# 11_RK3128_CODEC_HDMI_DAC.net
KiCad netlist of a schematic drawn in Altium Designer
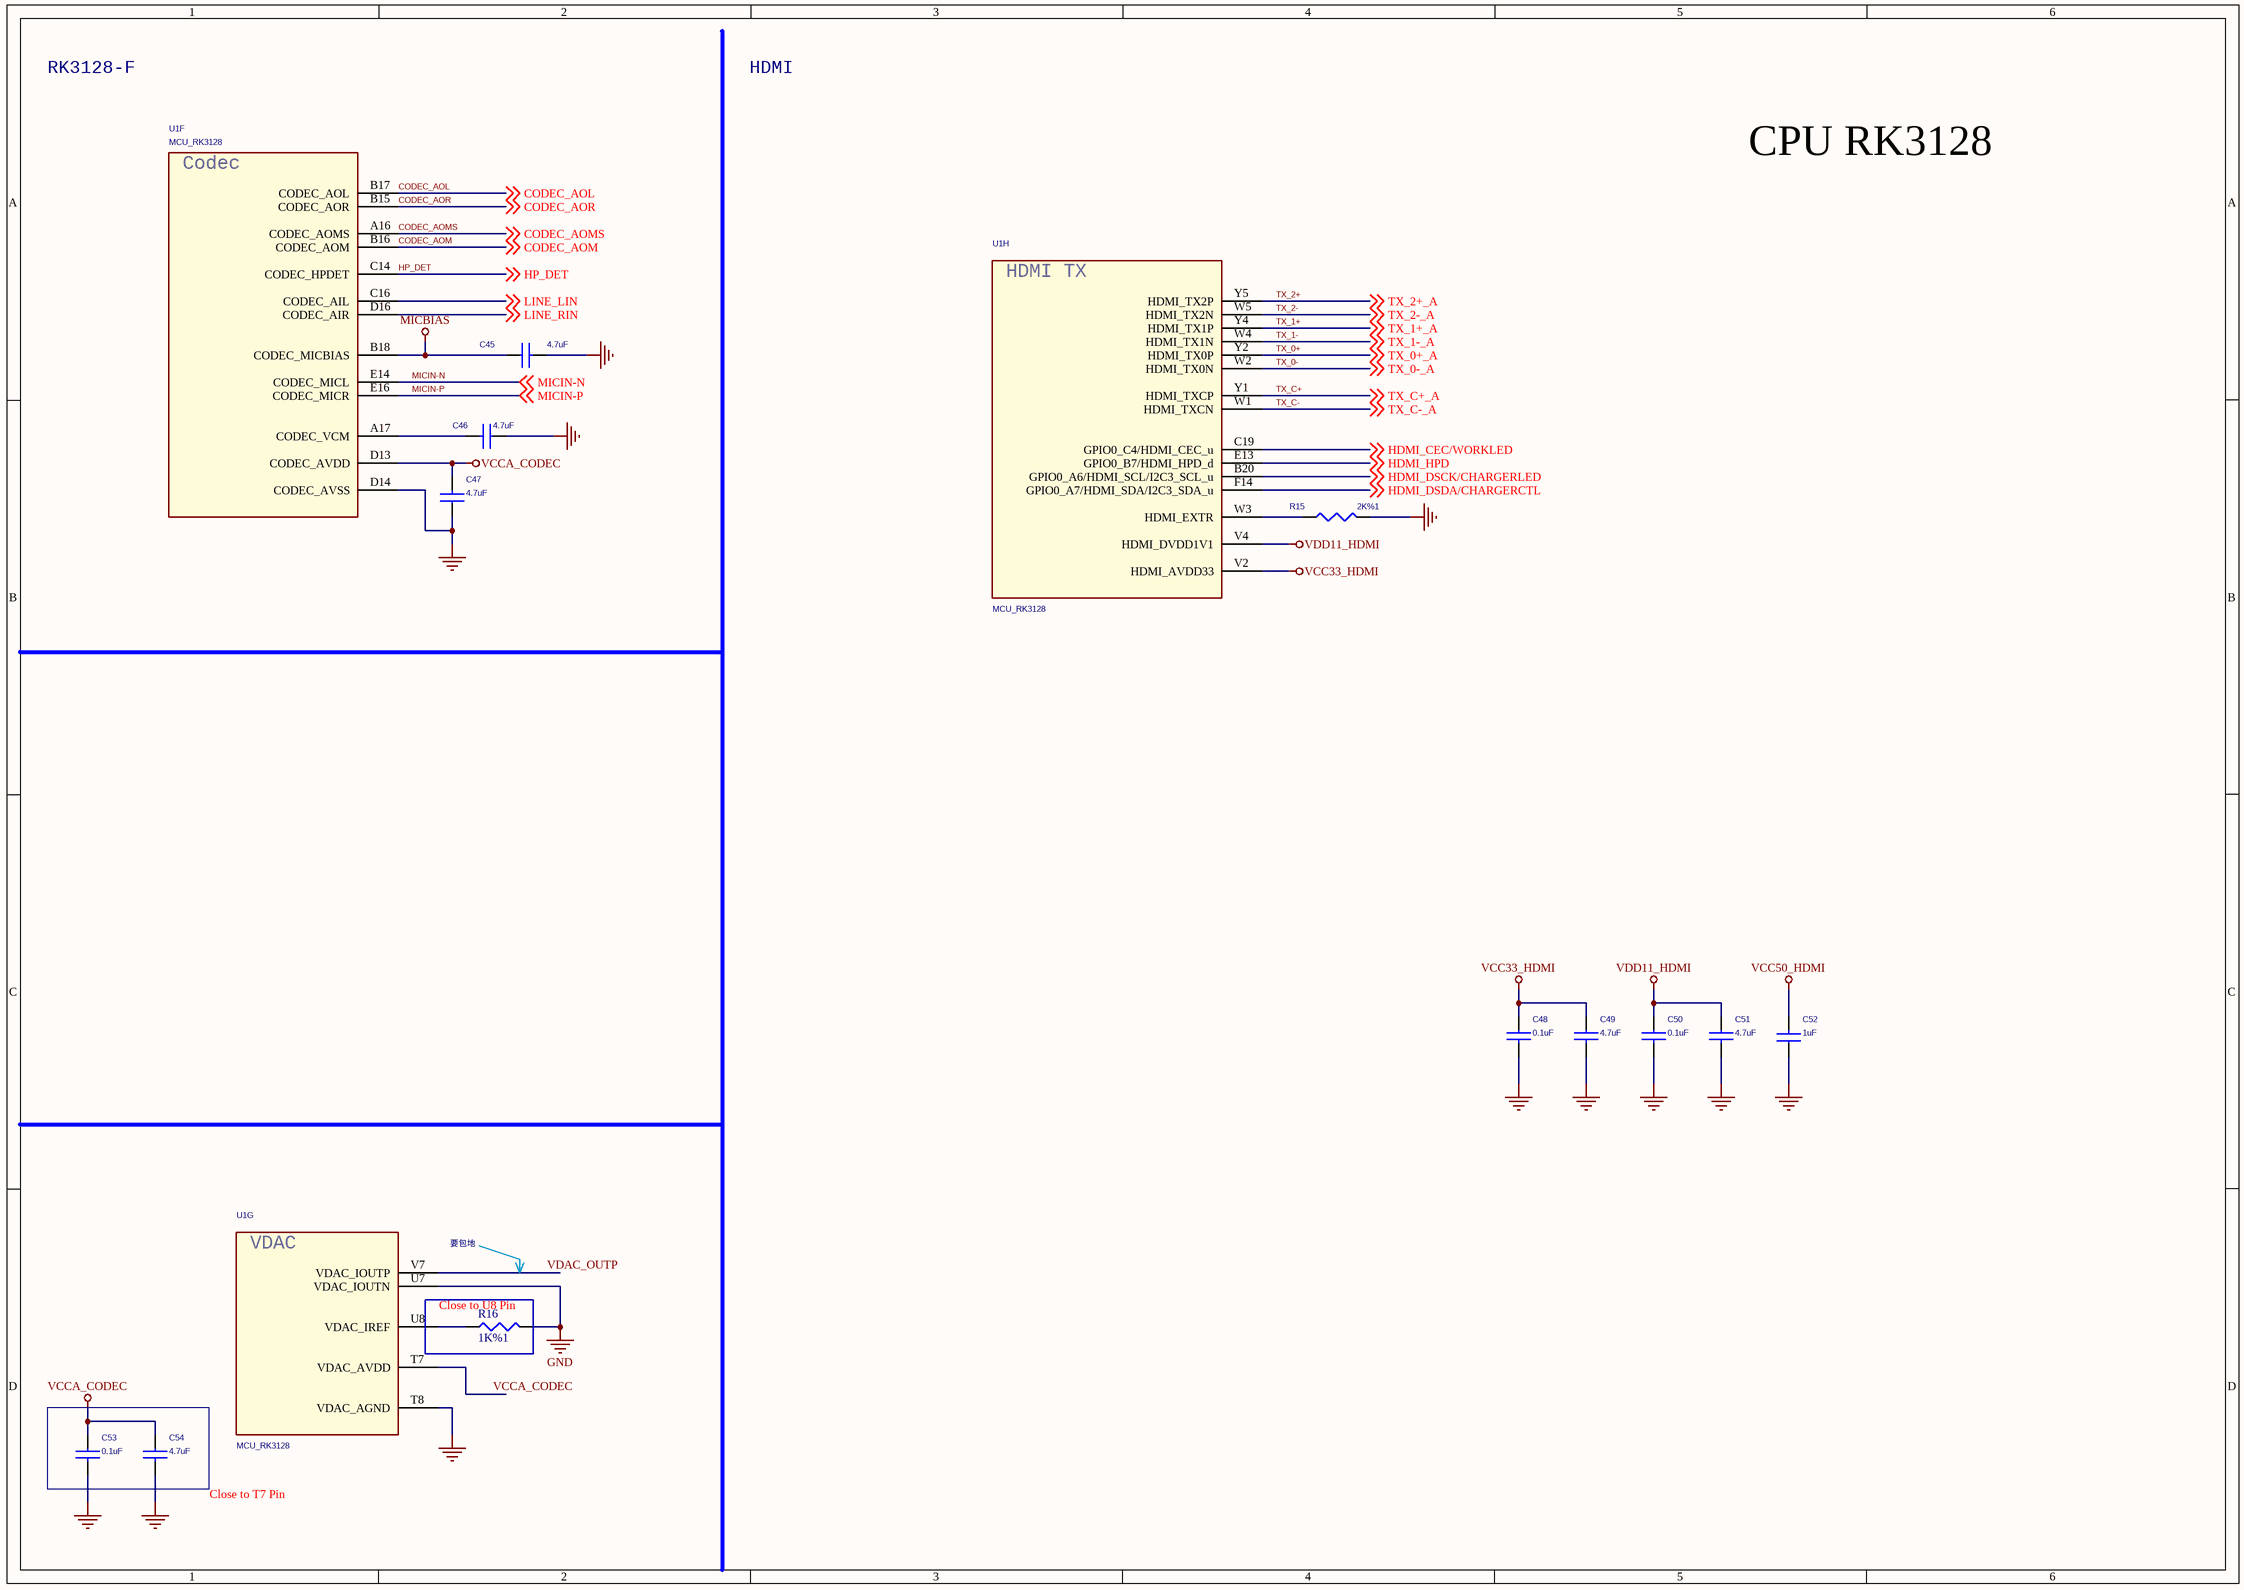
[diagram p0: 11_RK3128_CODEC_HDMI_DAC.SchDoc]

(export (version "E")
  (design (tool "Eeschema 10.0.6"))
  (components
    (comp (ref "C45") (value "4.7uF") (footprint "C0603") (libsource (lib "*") (part "CAP NP")))
    (comp (ref "C46")
      (value "4.7uF")
      (footprint "C0603")
      (description "CAP,MLCC,10uF,+/-10%,X5R,16V,SMD0805")
      (libsource (lib "*") (part "CAP NP"))
    )
    (comp (ref "C47")
      (value "4.7uF")
      (footprint "C0603")
      (description "RoHS CHIP CAP 0.1uF +10/-10% X7R")
      (libsource (lib "*") (part "CAP NP"))
    )
    (comp (ref "C48") (value "0.1uF") (footprint "C0402") (libsource (lib "*") (part "CAP NP")))
    (comp (ref "C49") (value "4.7uF") (footprint "C0603") (libsource (lib "*") (part "CAP NP")))
    (comp (ref "C50") (value "0.1uF") (footprint "C0402") (libsource (lib "*") (part "CAP NP")))
    (comp (ref "C51") (value "4.7uF") (footprint "C0603") (libsource (lib "*") (part "CAP NP")))
    (comp (ref "C52")
      (value "1uF")
      (footprint "C0402")
      (description "RoHS CHIP CAP 1uF +10/-10% X5R")
      (libsource (lib "*") (part "CAP NP"))
    )
    (comp (ref "C53") (value "0.1uF") (footprint "C0402") (libsource (lib "*") (part "CAP NP")))
    (comp (ref "C54") (value "4.7uF") (footprint "C0603") (libsource (lib "*") (part "CAP NP")))
    (comp (ref "R15")
      (value "2K%1")
      (footprint "R0402")
      (description "RES,thick film,3.5KOhm,+/-5%,1/16W,SMD0402")
      (libsource (lib "*") (part "RESISTOR_0"))
    )
    (comp (ref "R16")
      (value "1K%1")
      (footprint "R0402")
      (description "1K %1 R0402")
      (libsource (lib "RK3128_BETA_V03_20151231_Library") (part "RESISTOR"))
    )
    (comp (ref "U1")
      (value "MCU_RK3128")
      (footprint "BGA316-14X14-0.65")
      (libsource (lib "*") (part "MCU_RK3128"))
    )
  )
  (nets
    (net (code "1") (name "/VDAC_OUTP") (class "Default")
      (node (ref "U1") (pin "V7") (pinfunction "VDAC_IOUTP_V7") (pintype "passive"))
    )
    (net (code "2") (name "CODEC_AOL") (class "Default")
      (node (ref "U1") (pin "B17") (pinfunction "CODEC_AOL_B17") (pintype "passive"))
    )
    (net (code "3") (name "CODEC_AOM") (class "Default")
      (node (ref "U1") (pin "B16") (pinfunction "CODEC_AOM_B16") (pintype "passive"))
    )
    (net (code "4") (name "CODEC_AOMS") (class "Default")
      (node (ref "U1") (pin "A16") (pinfunction "CODEC_AOMS_A16") (pintype "passive"))
    )
    (net (code "5") (name "CODEC_AOR") (class "Default")
      (node (ref "U1") (pin "B15") (pinfunction "CODEC_AOR_B15") (pintype "passive"))
    )
    (net (code "6") (name "GND") (class "Default")
      (node (ref "C45") (pin "2") (pinfunction "2_2") (pintype "passive"))
      (node (ref "C46") (pin "1") (pinfunction "1_1") (pintype "passive"))
      (node (ref "C47") (pin "1") (pinfunction "1_1") (pintype "passive"))
      (node (ref "C48") (pin "2") (pinfunction "2_2") (pintype "passive"))
      (node (ref "C49") (pin "2") (pinfunction "2_2") (pintype "passive"))
      (node (ref "C50") (pin "2") (pinfunction "2_2") (pintype "passive"))
      (node (ref "C51") (pin "2") (pinfunction "2_2") (pintype "passive"))
      (node (ref "C52") (pin "1") (pinfunction "1_1") (pintype "passive"))
      (node (ref "C53") (pin "2") (pinfunction "2_2") (pintype "passive"))
      (node (ref "C54") (pin "2") (pinfunction "2_2") (pintype "passive"))
      (node (ref "R15") (pin "1") (pinfunction "1_1") (pintype "passive"))
      (node (ref "R16") (pin "2") (pinfunction "2_2") (pintype "passive"))
      (node (ref "U1") (pin "D14") (pinfunction "CODEC_AVSS_D14") (pintype "passive"))
      (node (ref "U1") (pin "T8") (pinfunction "VDAC_AGND_T8") (pintype "passive"))
      (node (ref "U1") (pin "U7") (pinfunction "VDAC_IOUTN_U7") (pintype "passive"))
    )
    (net (code "7") (name "HDMI_CEC{slash}WORKLED") (class "Default")
      (node (ref "U1") (pin "C19") (pinfunction "GPIO0_C4/HDMI_CEC_u_C19") (pintype "passive"))
    )
    (net (code "8") (name "HDMI_DSCK{slash}CHARGERLED") (class "Default")
      (node (ref "U1") (pin "B20") (pinfunction "GPIO0_A6/HDMI_SCL/I2C3_SCL_u_B20") (pintype "passive"))
    )
    (net (code "9") (name "HDMI_DSDA{slash}CHARGERCTL") (class "Default")
      (node (ref "U1") (pin "F14") (pinfunction "GPIO0_A7/HDMI_SDA/I2C3_SDA_u_F14") (pintype "passive"))
    )
    (net (code "10") (name "HDMI_HPD") (class "Default")
      (node (ref "U1") (pin "E13") (pinfunction "GPIO0_B7/HDMI_HPD_d_E13") (pintype "passive"))
    )
    (net (code "11") (name "HP_DET") (class "Default")
      (node (ref "U1") (pin "C14") (pinfunction "CODEC_HPDET_C14") (pintype "passive"))
    )
    (net (code "12") (name "LINE_LIN") (class "Default")
      (node (ref "U1") (pin "C16") (pinfunction "CODEC_AIL_C16") (pintype "passive"))
    )
    (net (code "13") (name "LINE_RIN") (class "Default")
      (node (ref "U1") (pin "D16") (pinfunction "CODEC_AIR_D16") (pintype "passive"))
    )
    (net (code "14") (name "MICBIAS") (class "Default")
      (node (ref "C45") (pin "1") (pinfunction "1_1") (pintype "passive"))
      (node (ref "U1") (pin "B18") (pinfunction "CODEC_MICBIAS_B18") (pintype "passive"))
    )
    (net (code "15") (name "MICIN-N") (class "Default")
      (node (ref "U1") (pin "E14") (pinfunction "CODEC_MICL_E14") (pintype "passive"))
    )
    (net (code "16") (name "MICIN-P") (class "Default")
      (node (ref "U1") (pin "E16") (pinfunction "CODEC_MICR_E16") (pintype "passive"))
    )
    (net (code "17") (name "Net-(U1F-CODEC_VCM)") (class "Default")
      (node (ref "C46") (pin "2") (pinfunction "2_2") (pintype "passive"))
      (node (ref "U1") (pin "A17") (pinfunction "CODEC_VCM_A17") (pintype "passive"))
    )
    (net (code "18") (name "Net-(U1G-VDAC_IREF)") (class "Default")
      (node (ref "R16") (pin "1") (pinfunction "1_1") (pintype "passive"))
      (node (ref "U1") (pin "U8") (pinfunction "VDAC_IREF_U8") (pintype "passive"))
    )
    (net (code "19") (name "Net-(U1H-HDMI_EXTR)") (class "Default")
      (node (ref "R15") (pin "2") (pinfunction "2_2") (pintype "passive"))
      (node (ref "U1") (pin "W3") (pinfunction "HDMI_EXTR_W3") (pintype "passive"))
    )
    (net (code "20") (name "TX_0+_A") (class "Default")
      (node (ref "U1") (pin "Y2") (pinfunction "HDMI_TX0P_Y2") (pintype "passive"))
    )
    (net (code "21") (name "TX_0-_A") (class "Default")
      (node (ref "U1") (pin "W2") (pinfunction "HDMI_TX0N_W2") (pintype "passive"))
    )
    (net (code "22") (name "TX_1+_A") (class "Default")
      (node (ref "U1") (pin "Y4") (pinfunction "HDMI_TX1P_Y4") (pintype "passive"))
    )
    (net (code "23") (name "TX_1-_A") (class "Default")
      (node (ref "U1") (pin "W4") (pinfunction "HDMI_TX1N_W4") (pintype "passive"))
    )
    (net (code "24") (name "TX_2+_A") (class "Default")
      (node (ref "U1") (pin "Y5") (pinfunction "HDMI_TX2P_Y5") (pintype "passive"))
    )
    (net (code "25") (name "TX_2-_A") (class "Default")
      (node (ref "U1") (pin "W5") (pinfunction "HDMI_TX2N_W5") (pintype "passive"))
    )
    (net (code "26") (name "TX_C+_A") (class "Default")
      (node (ref "U1") (pin "Y1") (pinfunction "HDMI_TXCP_Y1") (pintype "passive"))
    )
    (net (code "27") (name "TX_C-_A") (class "Default")
      (node (ref "U1") (pin "W1") (pinfunction "HDMI_TXCN_W1") (pintype "passive"))
    )
    (net (code "28") (name "VCC33_HDMI") (class "Default")
      (node (ref "C48") (pin "1") (pinfunction "1_1") (pintype "passive"))
      (node (ref "C49") (pin "1") (pinfunction "1_1") (pintype "passive"))
      (node (ref "U1") (pin "V2") (pinfunction "HDMI_AVDD33_V2") (pintype "passive"))
    )
    (net (code "29") (name "VCC50_HDMI") (class "Default")
      (node (ref "C52") (pin "2") (pinfunction "2_2") (pintype "passive"))
    )
    (net (code "30") (name "VCCA_CODEC") (class "Default")
      (node (ref "C47") (pin "2") (pinfunction "2_2") (pintype "passive"))
      (node (ref "C53") (pin "1") (pinfunction "1_1") (pintype "passive"))
      (node (ref "C54") (pin "1") (pinfunction "1_1") (pintype "passive"))
      (node (ref "U1") (pin "D13") (pinfunction "CODEC_AVDD_D13") (pintype "passive"))
      (node (ref "U1") (pin "T7") (pinfunction "VDAC_AVDD_T7") (pintype "passive"))
    )
    (net (code "31") (name "VDD11_HDMI") (class "Default")
      (node (ref "C50") (pin "1") (pinfunction "1_1") (pintype "passive"))
      (node (ref "C51") (pin "1") (pinfunction "1_1") (pintype "passive"))
      (node (ref "U1") (pin "V4") (pinfunction "HDMI_DVDD1V1_V4") (pintype "passive"))
    )
  )
)
